# USB.net
KiCad netlist of a schematic drawn in Altium Designer
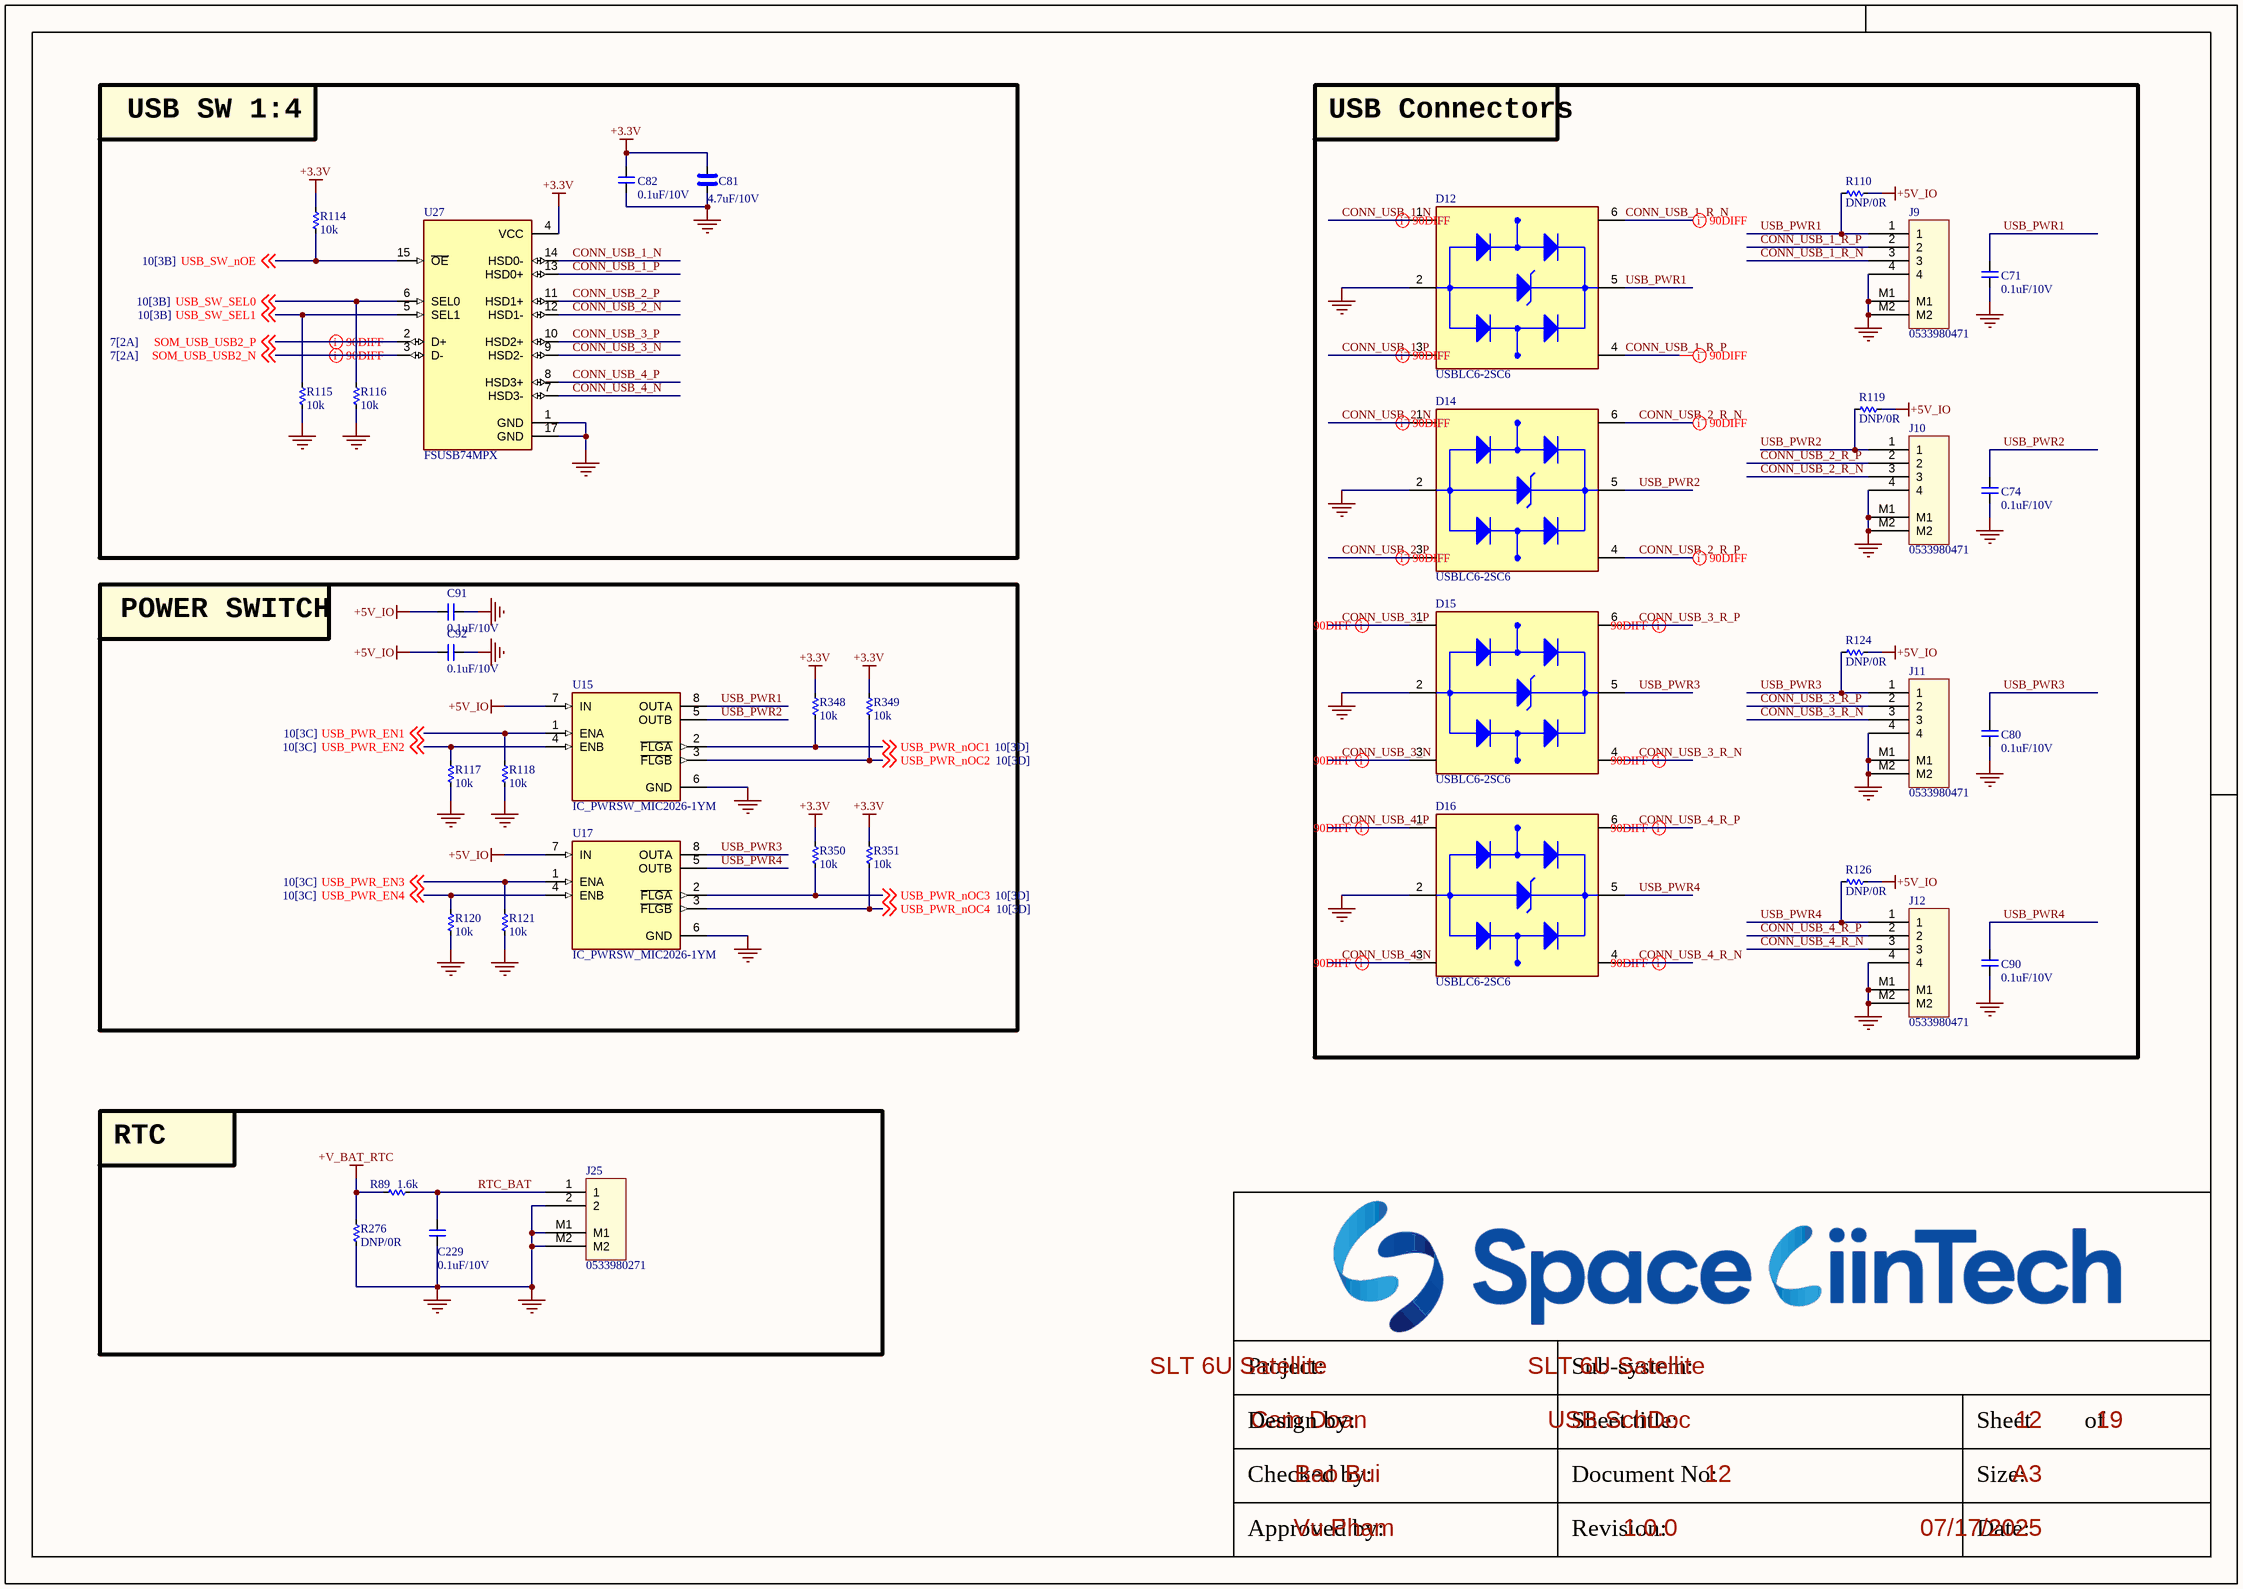
[diagram p0: USB.SchDoc]

(export (version "E")
  (design (tool "Eeschema 10.0.6"))
  (components
    (comp (ref "C71")
      (value "0.1uF/10V")
      (footprint "CAP_C_1005X60")
      (description "CAP CHIP")
      (libsource (lib "LABLIB") (part "_CAP_C_2"))
    )
    (comp (ref "C74")
      (value "0.1uF/10V")
      (footprint "CAP_C_1005X60")
      (description "CAP CHIP")
      (libsource (lib "LABLIB") (part "_CAP_C_2"))
    )
    (comp (ref "C80")
      (value "0.1uF/10V")
      (footprint "CAP_C_1005X60")
      (description "CAP CHIP")
      (libsource (lib "LABLIB") (part "_CAP_C_2"))
    )
    (comp (ref "C81")
      (value "4.7uF/10V")
      (footprint "CAP_C_1608X80")
      (description "CAP CHIP High Value")
      (libsource (lib "LABLIB") (part "_CAP_C_High_2"))
    )
    (comp (ref "C82")
      (value "0.1uF/10V")
      (footprint "CAP_C_1005X60")
      (description "CAP CHIP")
      (libsource (lib "LABLIB") (part "_CAP_C_2"))
    )
    (comp (ref "C90")
      (value "0.1uF/10V")
      (footprint "CAP_C_1005X60")
      (description "CAP CHIP")
      (libsource (lib "LABLIB") (part "_CAP_C_2"))
    )
    (comp (ref "C91")
      (value "0.1uF/10V")
      (footprint "CAP_C_1005X60")
      (description "CAP CHIP")
      (libsource (lib "LABLIB") (part "_CAP_C_2"))
    )
    (comp (ref "C92")
      (value "0.1uF/10V")
      (footprint "CAP_C_1005X60")
      (description "CAP CHIP")
      (libsource (lib "LABLIB") (part "_CAP_C_2"))
    )
    (comp (ref "C229")
      (value "0.1uF/10V")
      (footprint "CAP_C_1005X60")
      (description "CAP CHIP")
      (libsource (lib "LABLIB") (part "_CAP_C_2"))
    )
    (comp (ref "D12")
      (value "USBLC6-2SC6")
      (footprint "SOT95P280X145-6N")
      (description "17V Clamp 5A (8/20Âµs) Ipp Tvs Diode Surface Mount SOT-23-6")
      (fields (field (name "MF") "STMicroelectronics"))
      (libsource (lib "USBLC6-2SC6") (part "USBLC6-2SC6"))
    )
    (comp (ref "D14")
      (value "USBLC6-2SC6")
      (footprint "SOT95P280X145-6N")
      (description "17V Clamp 5A (8/20Âµs) Ipp Tvs Diode Surface Mount SOT-23-6")
      (fields (field (name "MF") "STMicroelectronics"))
      (libsource (lib "USBLC6-2SC6") (part "USBLC6-2SC6"))
    )
    (comp (ref "D15")
      (value "USBLC6-2SC6")
      (footprint "SOT95P280X145-6N")
      (description "17V Clamp 5A (8/20Âµs) Ipp Tvs Diode Surface Mount SOT-23-6")
      (fields (field (name "MF") "STMicroelectronics"))
      (libsource (lib "USBLC6-2SC6") (part "USBLC6-2SC6"))
    )
    (comp (ref "D16")
      (value "USBLC6-2SC6")
      (footprint "SOT95P280X145-6N")
      (description "17V Clamp 5A (8/20Âµs) Ipp Tvs Diode Surface Mount SOT-23-6")
      (fields (field (name "MF") "STMicroelectronics"))
      (libsource (lib "USBLC6-2SC6") (part "USBLC6-2SC6"))
    )
    (comp (ref "J9")
      (value "0533980471")
      (footprint "MOLEX_0533980471")
      (libsource (lib "LABLIB") (part "Header 4x1_2M"))
    )
    (comp (ref "J10")
      (value "0533980471")
      (footprint "MOLEX_0533980471")
      (libsource (lib "LABLIB") (part "Header 4x1_2M"))
    )
    (comp (ref "J11")
      (value "0533980471")
      (footprint "MOLEX_0533980471")
      (libsource (lib "LABLIB") (part "Header 4x1_2M"))
    )
    (comp (ref "J12")
      (value "0533980471")
      (footprint "MOLEX_0533980471")
      (libsource (lib "LABLIB") (part "Header 4x1_2M"))
    )
    (comp (ref "J25")
      (value "0533980271")
      (footprint "MOLEX_0533980271")
      (libsource (lib "LABLIB") (part "Header 2x1_2M"))
    )
    (comp (ref "R89")
      (value "1.6k")
      (footprint "RES_C_1005X40")
      (description "RES")
      (libsource (lib "LABLIB") (part "_RES_B_2"))
    )
    (comp (ref "R110")
      (value "DNP/0R")
      (footprint "RES_C_1005X40")
      (description "RES")
      (libsource (lib "LABLIB") (part "_RES_B_2"))
    )
    (comp (ref "R114")
      (value "10k")
      (footprint "RES_C_1005X40")
      (description "RES")
      (libsource (lib "LABLIB") (part "_RES_B_2"))
    )
    (comp (ref "R115")
      (value "10k")
      (footprint "RES_C_1005X40")
      (description "RES")
      (libsource (lib "LABLIB") (part "_RES_B_2"))
    )
    (comp (ref "R116")
      (value "10k")
      (footprint "RES_C_1005X40")
      (description "RES")
      (libsource (lib "LABLIB") (part "_RES_B_2"))
    )
    (comp (ref "R117")
      (value "10k")
      (footprint "RES_C_1005X40")
      (description "RES")
      (libsource (lib "LABLIB") (part "_RES_B_2"))
    )
    (comp (ref "R118")
      (value "10k")
      (footprint "RES_C_1005X40")
      (description "RES")
      (libsource (lib "LABLIB") (part "_RES_B_2"))
    )
    (comp (ref "R119")
      (value "DNP/0R")
      (footprint "RES_C_1005X40")
      (description "RES")
      (libsource (lib "LABLIB") (part "_RES_B_2"))
    )
    (comp (ref "R120")
      (value "10k")
      (footprint "RES_C_1005X40")
      (description "RES")
      (libsource (lib "LABLIB") (part "_RES_B_2"))
    )
    (comp (ref "R121")
      (value "10k")
      (footprint "RES_C_1005X40")
      (description "RES")
      (libsource (lib "LABLIB") (part "_RES_B_2"))
    )
    (comp (ref "R124")
      (value "DNP/0R")
      (footprint "RES_C_1005X40")
      (description "RES")
      (libsource (lib "LABLIB") (part "_RES_B_2"))
    )
    (comp (ref "R126")
      (value "DNP/0R")
      (footprint "RES_C_1005X40")
      (description "RES")
      (libsource (lib "LABLIB") (part "_RES_B_2"))
    )
    (comp (ref "R276")
      (value "DNP/0R")
      (footprint "RES_C_1005X40")
      (description "RES")
      (libsource (lib "LABLIB") (part "_RES_B_2"))
    )
    (comp (ref "R348")
      (value "10k")
      (footprint "RES_C_1005X40")
      (description "RES")
      (libsource (lib "LABLIB") (part "_RES_B_2"))
    )
    (comp (ref "R349")
      (value "10k")
      (footprint "RES_C_1005X40")
      (description "RES")
      (libsource (lib "LABLIB") (part "_RES_B_2"))
    )
    (comp (ref "R350")
      (value "10k")
      (footprint "RES_C_1005X40")
      (description "RES")
      (libsource (lib "LABLIB") (part "_RES_B_2"))
    )
    (comp (ref "R351")
      (value "10k")
      (footprint "RES_C_1005X40")
      (description "RES")
      (libsource (lib "LABLIB") (part "_RES_B_2"))
    )
    (comp (ref "U15")
      (value "IC_PWRSW_MIC2026-1YM")
      (footprint "SOIC127P602X173-8N")
      (description "Power Switch/Driver 1:2 N-Channel 1.25A 8-SOIC")
      (fields (field (name "MF") "Microchip") (field (name "MP") "MIC2026-1YM"))
      (libsource (lib "LABLIB") (part "IC_PWRSW_MIC2026-1YM"))
    )
    (comp (ref "U17")
      (value "IC_PWRSW_MIC2026-1YM")
      (footprint "SOIC127P602X173-8N")
      (description "Power Switch/Driver 1:2 N-Channel 1.25A 8-SOIC")
      (fields (field (name "MF") "Microchip") (field (name "MP") "MIC2026-1YM"))
      (libsource (lib "LABLIB") (part "IC_PWRSW_MIC2026-1YM"))
    )
    (comp (ref "U27")
      (value "FSUSB74MPX")
      (footprint "QFN50P300X300X80-17N")
      (description "USB Switch IC 1 Channel 16-MLP (3x3)")
      (fields (field (name "MF") "ON Semiconductor"))
      (libsource (lib "LABLIB") (part "IC_USB_SW_FSUSB74MPX"))
    )
  )
  (nets
    (net (code "1") (name "+3.3V") (class "Default")
      (node (ref "C81") (pin "2") (pinfunction "2_2") (pintype "passive"))
      (node (ref "C82") (pin "2") (pinfunction "2_2") (pintype "passive"))
      (node (ref "R114") (pin "1") (pinfunction "1_1") (pintype "passive"))
      (node (ref "R348") (pin "1") (pinfunction "1_1") (pintype "passive"))
      (node (ref "R349") (pin "1") (pinfunction "1_1") (pintype "passive"))
      (node (ref "R350") (pin "1") (pinfunction "1_1") (pintype "passive"))
      (node (ref "R351") (pin "1") (pinfunction "1_1") (pintype "passive"))
      (node (ref "U27") (pin "4") (pinfunction "VCC_4") (pintype "power_in"))
    )
    (net (code "2") (name "+5V_IO") (class "Default")
      (node (ref "C91") (pin "2") (pinfunction "2_2") (pintype "passive"))
      (node (ref "C92") (pin "2") (pinfunction "2_2") (pintype "passive"))
      (node (ref "R110") (pin "1") (pinfunction "1_1") (pintype "passive"))
      (node (ref "R119") (pin "1") (pinfunction "1_1") (pintype "passive"))
      (node (ref "R124") (pin "1") (pinfunction "1_1") (pintype "passive"))
      (node (ref "R126") (pin "1") (pinfunction "1_1") (pintype "passive"))
      (node (ref "U15") (pin "7") (pinfunction "IN_7") (pintype "input"))
      (node (ref "U17") (pin "7") (pinfunction "IN_7") (pintype "input"))
    )
    (net (code "3") (name "+V_BAT_RTC") (class "Default")
      (node (ref "R276") (pin "1") (pinfunction "1_1") (pintype "passive"))
      (node (ref "R89") (pin "1") (pinfunction "1_1") (pintype "passive"))
    )
    (net (code "4") (name "/CONN_USB_1_N") (class "Default")
      (node (ref "D12") (pin "1") (pinfunction "I/O1_IN_1") (pintype "passive"))
      (node (ref "U27") (pin "14") (pinfunction "HSD0-_14") (pintype "bidirectional"))
    )
    (net (code "5") (name "/CONN_USB_1_P") (class "Default")
      (node (ref "D12") (pin "3") (pinfunction "I/O2_IN_3") (pintype "passive"))
      (node (ref "U27") (pin "13") (pinfunction "HSD0+_13") (pintype "bidirectional"))
    )
    (net (code "6") (name "/CONN_USB_1_R_N") (class "Default")
      (node (ref "D12") (pin "6") (pinfunction "I/O1_OUT_6") (pintype "passive"))
      (node (ref "J9") (pin "3") (pinfunction "3_3") (pintype "passive"))
    )
    (net (code "7") (name "/CONN_USB_1_R_P") (class "Default")
      (node (ref "D12") (pin "4") (pinfunction "I/O2_OUT_4") (pintype "passive"))
      (node (ref "J9") (pin "2") (pinfunction "2_2") (pintype "passive"))
    )
    (net (code "8") (name "/CONN_USB_2_N") (class "Default")
      (node (ref "D14") (pin "1") (pinfunction "I/O1_IN_1") (pintype "passive"))
      (node (ref "U27") (pin "12") (pinfunction "HSD1-_12") (pintype "bidirectional"))
    )
    (net (code "9") (name "/CONN_USB_2_P") (class "Default")
      (node (ref "D14") (pin "3") (pinfunction "I/O2_IN_3") (pintype "passive"))
      (node (ref "U27") (pin "11") (pinfunction "HSD1+_11") (pintype "bidirectional"))
    )
    (net (code "10") (name "/CONN_USB_2_R_N") (class "Default")
      (node (ref "D14") (pin "6") (pinfunction "I/O1_OUT_6") (pintype "passive"))
      (node (ref "J10") (pin "3") (pinfunction "3_3") (pintype "passive"))
    )
    (net (code "11") (name "/CONN_USB_2_R_P") (class "Default")
      (node (ref "D14") (pin "4") (pinfunction "I/O2_OUT_4") (pintype "passive"))
      (node (ref "J10") (pin "2") (pinfunction "2_2") (pintype "passive"))
    )
    (net (code "12") (name "/CONN_USB_3_N") (class "Default")
      (node (ref "D15") (pin "3") (pinfunction "I/O2_IN_3") (pintype "passive"))
      (node (ref "U27") (pin "9") (pinfunction "HSD2-_9") (pintype "bidirectional"))
    )
    (net (code "13") (name "/CONN_USB_3_P") (class "Default")
      (node (ref "D15") (pin "1") (pinfunction "I/O1_IN_1") (pintype "passive"))
      (node (ref "U27") (pin "10") (pinfunction "HSD2+_10") (pintype "bidirectional"))
    )
    (net (code "14") (name "/CONN_USB_3_R_N") (class "Default")
      (node (ref "D15") (pin "4") (pinfunction "I/O2_OUT_4") (pintype "passive"))
      (node (ref "J11") (pin "3") (pinfunction "3_3") (pintype "passive"))
    )
    (net (code "15") (name "/CONN_USB_3_R_P") (class "Default")
      (node (ref "D15") (pin "6") (pinfunction "I/O1_OUT_6") (pintype "passive"))
      (node (ref "J11") (pin "2") (pinfunction "2_2") (pintype "passive"))
    )
    (net (code "16") (name "/CONN_USB_4_N") (class "Default")
      (node (ref "D16") (pin "3") (pinfunction "I/O2_IN_3") (pintype "passive"))
      (node (ref "U27") (pin "7") (pinfunction "HSD3-_7") (pintype "bidirectional"))
    )
    (net (code "17") (name "/CONN_USB_4_P") (class "Default")
      (node (ref "D16") (pin "1") (pinfunction "I/O1_IN_1") (pintype "passive"))
      (node (ref "U27") (pin "8") (pinfunction "HSD3+_8") (pintype "bidirectional"))
    )
    (net (code "18") (name "/CONN_USB_4_R_N") (class "Default")
      (node (ref "D16") (pin "4") (pinfunction "I/O2_OUT_4") (pintype "passive"))
      (node (ref "J12") (pin "3") (pinfunction "3_3") (pintype "passive"))
    )
    (net (code "19") (name "/CONN_USB_4_R_P") (class "Default")
      (node (ref "D16") (pin "6") (pinfunction "I/O1_OUT_6") (pintype "passive"))
      (node (ref "J12") (pin "2") (pinfunction "2_2") (pintype "passive"))
    )
    (net (code "20") (name "/RTC_BAT") (class "Default")
      (node (ref "C229") (pin "2") (pinfunction "2_2") (pintype "passive"))
      (node (ref "J25") (pin "1") (pinfunction "1_1") (pintype "passive"))
      (node (ref "R89") (pin "2") (pinfunction "2_2") (pintype "passive"))
    )
    (net (code "21") (name "/USB_PWR1") (class "Default")
      (node (ref "C71") (pin "2") (pinfunction "2_2") (pintype "passive"))
      (node (ref "D12") (pin "5") (pinfunction "VBUS_5") (pintype "power_in"))
      (node (ref "J9") (pin "1") (pinfunction "1_1") (pintype "passive"))
      (node (ref "R110") (pin "2") (pinfunction "2_2") (pintype "passive"))
      (node (ref "U15") (pin "8") (pinfunction "OUTA_8") (pintype "passive"))
    )
    (net (code "22") (name "/USB_PWR2") (class "Default")
      (node (ref "C74") (pin "2") (pinfunction "2_2") (pintype "passive"))
      (node (ref "D14") (pin "5") (pinfunction "VBUS_5") (pintype "power_in"))
      (node (ref "J10") (pin "1") (pinfunction "1_1") (pintype "passive"))
      (node (ref "R119") (pin "2") (pinfunction "2_2") (pintype "passive"))
      (node (ref "U15") (pin "5") (pinfunction "OUTB_5") (pintype "passive"))
    )
    (net (code "23") (name "/USB_PWR3") (class "Default")
      (node (ref "C80") (pin "2") (pinfunction "2_2") (pintype "passive"))
      (node (ref "D15") (pin "5") (pinfunction "VBUS_5") (pintype "power_in"))
      (node (ref "J11") (pin "1") (pinfunction "1_1") (pintype "passive"))
      (node (ref "R124") (pin "2") (pinfunction "2_2") (pintype "passive"))
      (node (ref "U17") (pin "8") (pinfunction "OUTA_8") (pintype "passive"))
    )
    (net (code "24") (name "/USB_PWR4") (class "Default")
      (node (ref "C90") (pin "2") (pinfunction "2_2") (pintype "passive"))
      (node (ref "D16") (pin "5") (pinfunction "VBUS_5") (pintype "power_in"))
      (node (ref "J12") (pin "1") (pinfunction "1_1") (pintype "passive"))
      (node (ref "R126") (pin "2") (pinfunction "2_2") (pintype "passive"))
      (node (ref "U17") (pin "5") (pinfunction "OUTB_5") (pintype "passive"))
    )
    (net (code "25") (name "GND") (class "Default")
      (node (ref "C229") (pin "1") (pinfunction "1_1") (pintype "passive"))
      (node (ref "C71") (pin "1") (pinfunction "1_1") (pintype "passive"))
      (node (ref "C74") (pin "1") (pinfunction "1_1") (pintype "passive"))
      (node (ref "C80") (pin "1") (pinfunction "1_1") (pintype "passive"))
      (node (ref "C81") (pin "1") (pinfunction "1_1") (pintype "passive"))
      (node (ref "C82") (pin "1") (pinfunction "1_1") (pintype "passive"))
      (node (ref "C90") (pin "1") (pinfunction "1_1") (pintype "passive"))
      (node (ref "C91") (pin "1") (pinfunction "1_1") (pintype "passive"))
      (node (ref "C92") (pin "1") (pinfunction "1_1") (pintype "passive"))
      (node (ref "D12") (pin "2") (pinfunction "GND_2") (pintype "power_in"))
      (node (ref "D14") (pin "2") (pinfunction "GND_2") (pintype "power_in"))
      (node (ref "D15") (pin "2") (pinfunction "GND_2") (pintype "power_in"))
      (node (ref "D16") (pin "2") (pinfunction "GND_2") (pintype "power_in"))
      (node (ref "J10") (pin "4") (pinfunction "4_4") (pintype "passive"))
      (node (ref "J10") (pin "M1") (pinfunction "M1_M1") (pintype "passive"))
      (node (ref "J10") (pin "M2") (pinfunction "M2_M2") (pintype "passive"))
      (node (ref "J11") (pin "4") (pinfunction "4_4") (pintype "passive"))
      (node (ref "J11") (pin "M1") (pinfunction "M1_M1") (pintype "passive"))
      (node (ref "J11") (pin "M2") (pinfunction "M2_M2") (pintype "passive"))
      (node (ref "J12") (pin "4") (pinfunction "4_4") (pintype "passive"))
      (node (ref "J12") (pin "M1") (pinfunction "M1_M1") (pintype "passive"))
      (node (ref "J12") (pin "M2") (pinfunction "M2_M2") (pintype "passive"))
      (node (ref "J25") (pin "2") (pinfunction "2_2") (pintype "passive"))
      (node (ref "J25") (pin "M1") (pinfunction "M1_M1") (pintype "passive"))
      (node (ref "J25") (pin "M2") (pinfunction "M2_M2") (pintype "passive"))
      (node (ref "J9") (pin "4") (pinfunction "4_4") (pintype "passive"))
      (node (ref "J9") (pin "M1") (pinfunction "M1_M1") (pintype "passive"))
      (node (ref "J9") (pin "M2") (pinfunction "M2_M2") (pintype "passive"))
      (node (ref "R115") (pin "2") (pinfunction "2_2") (pintype "passive"))
      (node (ref "R116") (pin "2") (pinfunction "2_2") (pintype "passive"))
      (node (ref "R117") (pin "2") (pinfunction "2_2") (pintype "passive"))
      (node (ref "R118") (pin "2") (pinfunction "2_2") (pintype "passive"))
      (node (ref "R120") (pin "2") (pinfunction "2_2") (pintype "passive"))
      (node (ref "R121") (pin "2") (pinfunction "2_2") (pintype "passive"))
      (node (ref "R276") (pin "2") (pinfunction "2_2") (pintype "passive"))
      (node (ref "U15") (pin "6") (pinfunction "GND_6") (pintype "power_in"))
      (node (ref "U17") (pin "6") (pinfunction "GND_6") (pintype "power_in"))
      (node (ref "U27") (pin "1") (pinfunction "GND_1") (pintype "power_in"))
      (node (ref "U27") (pin "17") (pinfunction "GND_17") (pintype "power_in"))
    )
    (net (code "26") (name "SOM_USB_USB2_N") (class "Default")
      (node (ref "U27") (pin "3") (pinfunction "D-_3") (pintype "bidirectional"))
    )
    (net (code "27") (name "SOM_USB_USB2_P") (class "Default")
      (node (ref "U27") (pin "2") (pinfunction "D+_2") (pintype "bidirectional"))
    )
    (net (code "28") (name "USB_PWR_EN1") (class "Default")
      (node (ref "R118") (pin "1") (pinfunction "1_1") (pintype "passive"))
      (node (ref "U15") (pin "1") (pinfunction "ENA_1") (pintype "input"))
    )
    (net (code "29") (name "USB_PWR_EN2") (class "Default")
      (node (ref "R117") (pin "1") (pinfunction "1_1") (pintype "passive"))
      (node (ref "U15") (pin "4") (pinfunction "ENB_4") (pintype "input"))
    )
    (net (code "30") (name "USB_PWR_EN3") (class "Default")
      (node (ref "R121") (pin "1") (pinfunction "1_1") (pintype "passive"))
      (node (ref "U17") (pin "1") (pinfunction "ENA_1") (pintype "input"))
    )
    (net (code "31") (name "USB_PWR_EN4") (class "Default")
      (node (ref "R120") (pin "1") (pinfunction "1_1") (pintype "passive"))
      (node (ref "U17") (pin "4") (pinfunction "ENB_4") (pintype "input"))
    )
    (net (code "32") (name "USB_PWR_nOC1") (class "Default")
      (node (ref "R348") (pin "2") (pinfunction "2_2") (pintype "passive"))
      (node (ref "U15") (pin "2") (pinfunction "~{FLGA}_2") (pintype "output"))
    )
    (net (code "33") (name "USB_PWR_nOC2") (class "Default")
      (node (ref "R349") (pin "2") (pinfunction "2_2") (pintype "passive"))
      (node (ref "U15") (pin "3") (pinfunction "~{FLGB}_3") (pintype "output"))
    )
    (net (code "34") (name "USB_PWR_nOC3") (class "Default")
      (node (ref "R350") (pin "2") (pinfunction "2_2") (pintype "passive"))
      (node (ref "U17") (pin "2") (pinfunction "~{FLGA}_2") (pintype "output"))
    )
    (net (code "35") (name "USB_PWR_nOC4") (class "Default")
      (node (ref "R351") (pin "2") (pinfunction "2_2") (pintype "passive"))
      (node (ref "U17") (pin "3") (pinfunction "~{FLGB}_3") (pintype "output"))
    )
    (net (code "36") (name "USB_SW_SEL0") (class "Default")
      (node (ref "R116") (pin "1") (pinfunction "1_1") (pintype "passive"))
      (node (ref "U27") (pin "6") (pinfunction "SEL0_6") (pintype "input"))
    )
    (net (code "37") (name "USB_SW_SEL1") (class "Default")
      (node (ref "R115") (pin "1") (pinfunction "1_1") (pintype "passive"))
      (node (ref "U27") (pin "5") (pinfunction "SEL1_5") (pintype "input"))
    )
    (net (code "38") (name "USB_SW_nOE") (class "Default")
      (node (ref "R114") (pin "2") (pinfunction "2_2") (pintype "passive"))
      (node (ref "U27") (pin "15") (pinfunction "~{OE}_15") (pintype "input"))
    )
  )
)
